# Part11_I2S_WM8960.net
KiCad netlist of a schematic drawn in Altium Designer
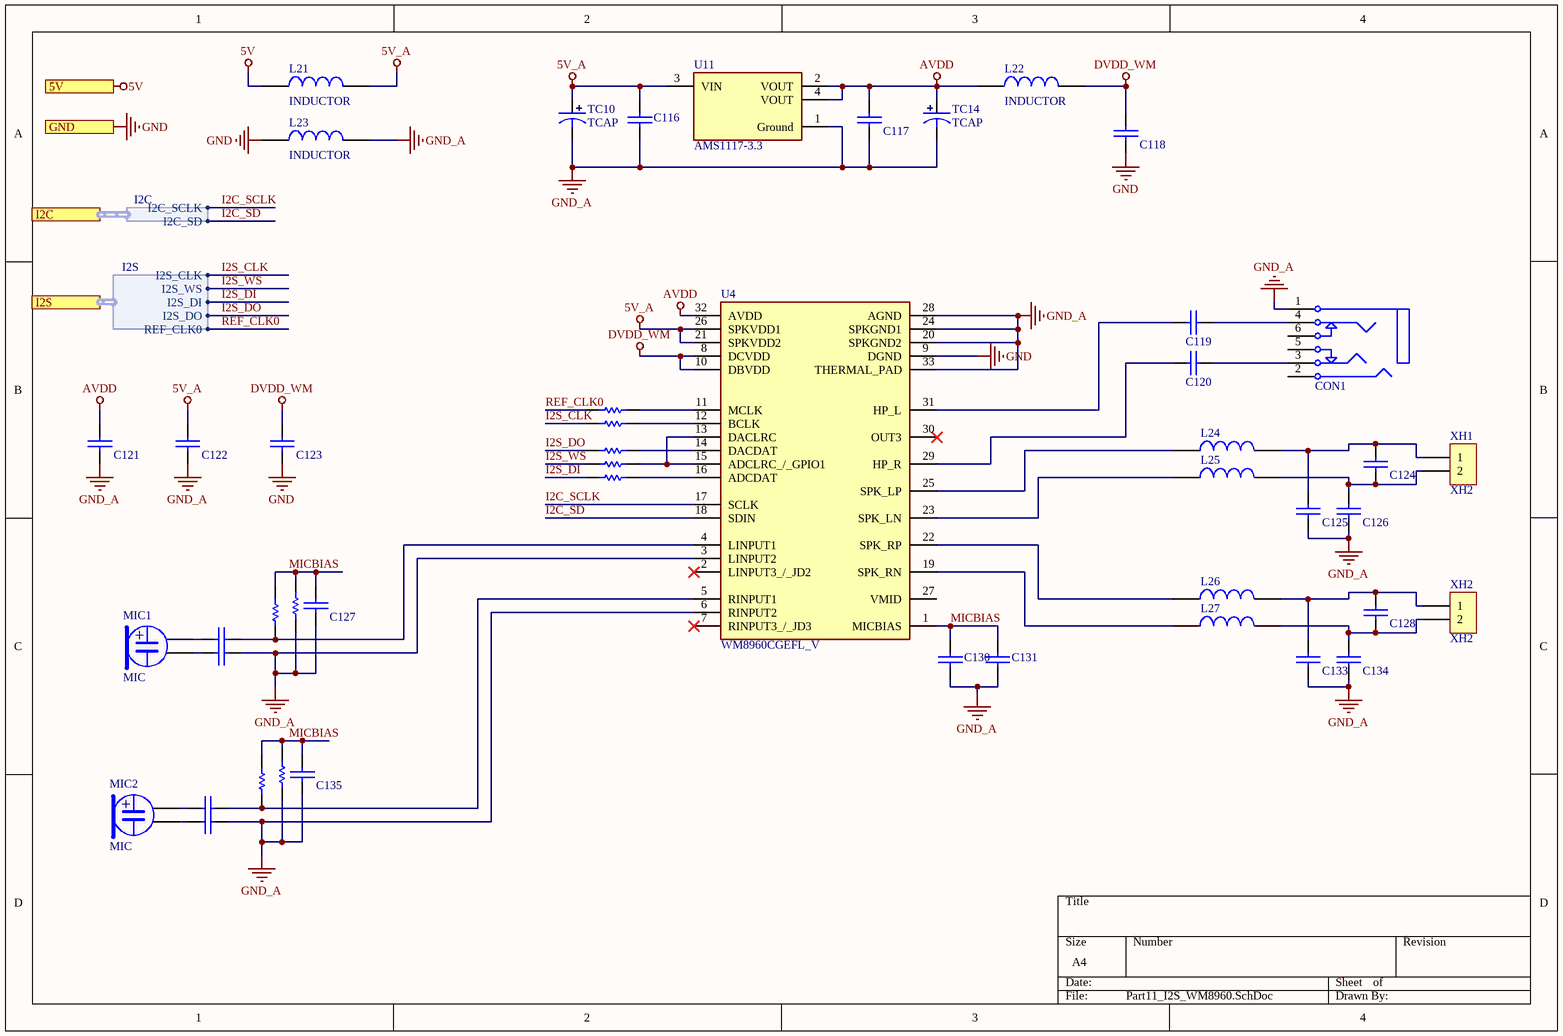
[diagram p0: Part11_I2S_WM8960.SchDoc]

(export (version "E")
  (design (tool "Eeschema 10.0.6"))
  (components
    (comp (ref "C116")
      (value "100nF")
      (footprint "0603C")
      (description "无极性电容")
      (libsource (lib "电容") (part "CAP"))
    )
    (comp (ref "C117")
      (value "100nF")
      (footprint "0603C")
      (description "无极性电容")
      (libsource (lib "电容") (part "CAP"))
    )
    (comp (ref "C118")
      (value "100nF")
      (footprint "0402C")
      (description "无极性电容")
      (libsource (lib "电容") (part "CAP"))
    )
    (comp (ref "C119")
      (value "100nF")
      (footprint "1206C")
      (description "无极性电容")
      (libsource (lib "电容") (part "CAP"))
    )
    (comp (ref "C120")
      (value "100nF")
      (footprint "1206C")
      (description "无极性电容")
      (libsource (lib "电容") (part "CAP"))
    )
    (comp (ref "C121")
      (value "100nF")
      (footprint "0603C")
      (description "无极性电容")
      (libsource (lib "电容") (part "CAP"))
    )
    (comp (ref "C122")
      (value "100nF")
      (footprint "0603C")
      (description "无极性电容")
      (libsource (lib "电容") (part "CAP"))
    )
    (comp (ref "C123")
      (value "100nF")
      (footprint "0603C")
      (description "无极性电容")
      (libsource (lib "电容") (part "CAP"))
    )
    (comp (ref "C124")
      (value "100nF")
      (footprint "1206C")
      (description "无极性电容")
      (libsource (lib "电容") (part "CAP"))
    )
    (comp (ref "C125")
      (value "100nF")
      (footprint "1206C")
      (description "无极性电容")
      (libsource (lib "电容") (part "CAP"))
    )
    (comp (ref "C126")
      (value "100nF")
      (footprint "1206C")
      (description "无极性电容")
      (libsource (lib "电容") (part "CAP"))
    )
    (comp (ref "C127")
      (value "100nF")
      (footprint "0603C")
      (description "无极性电容")
      (libsource (lib "电容") (part "CAP"))
    )
    (comp (ref "C128")
      (value "100nF")
      (footprint "1206C")
      (description "无极性电容")
      (libsource (lib "电容") (part "CAP"))
    )
    (comp (ref "C129")
      (value "100nF")
      (footprint "0603C")
      (description "无极性电容")
      (libsource (lib "电容") (part "CAP"))
    )
    (comp (ref "C130")
      (value "100nF")
      (footprint "0402C")
      (description "无极性电容")
      (libsource (lib "电容") (part "CAP"))
    )
    (comp (ref "C131")
      (value "100nF")
      (footprint "0402C")
      (description "无极性电容")
      (libsource (lib "电容") (part "CAP"))
    )
    (comp (ref "C132")
      (value "100nF")
      (footprint "0603C")
      (description "无极性电容")
      (libsource (lib "电容") (part "CAP"))
    )
    (comp (ref "C133")
      (value "100nF")
      (footprint "1206C")
      (description "无极性电容")
      (libsource (lib "电容") (part "CAP"))
    )
    (comp (ref "C134")
      (value "100nF")
      (footprint "1206C")
      (description "无极性电容")
      (libsource (lib "电容") (part "CAP"))
    )
    (comp (ref "C135")
      (value "100nF")
      (footprint "0603C")
      (description "无极性电容")
      (libsource (lib "电容") (part "CAP"))
    )
    (comp (ref "C136")
      (value "100nF")
      (footprint "0603C")
      (description "无极性电容")
      (libsource (lib "电容") (part "CAP"))
    )
    (comp (ref "C137")
      (value "100nF")
      (footprint "0603C")
      (description "无极性电容")
      (libsource (lib "电容") (part "CAP"))
    )
    (comp (ref "CON1")
      (value "PJ342")
      (footprint "PJ342A")
      (description "3.5耳机插座,4Pin")
      (fields (field (name "版权归属") "源创客"))
      (libsource (lib "音频插座") (part "PJ342"))
    )
    (comp (ref "L21") (value "INDUCTOR") (footprint "0805L") (libsource (lib "电感") (part "INDUCTOR")))
    (comp (ref "L22") (value "INDUCTOR") (footprint "0805L") (libsource (lib "电感") (part "INDUCTOR")))
    (comp (ref "L23") (value "INDUCTOR") (footprint "0805L") (libsource (lib "电感") (part "INDUCTOR")))
    (comp (ref "L24") (value "INDUCTOR") (footprint "0805L") (libsource (lib "电感") (part "INDUCTOR")))
    (comp (ref "L25") (value "INDUCTOR") (footprint "0805L") (libsource (lib "电感") (part "INDUCTOR")))
    (comp (ref "L26") (value "INDUCTOR") (footprint "0805L") (libsource (lib "电感") (part "INDUCTOR")))
    (comp (ref "L27") (value "INDUCTOR") (footprint "0805L") (libsource (lib "电感") (part "INDUCTOR")))
    (comp (ref "MIC1")
      (value "MIC")
      (footprint "MIC-4.5X1.9")
      (description "电容麦克风")
      (libsource (lib "传感器") (part "MIC"))
    )
    (comp (ref "MIC2")
      (value "MIC")
      (footprint "MIC-4.5X1.9")
      (description "电容麦克风")
      (libsource (lib "传感器") (part "MIC"))
    )
    (comp (ref "R21") (value "0R") (footprint "0402R") (libsource (lib "电阻") (part "RES")))
    (comp (ref "R22") (value "0R") (footprint "0402R") (libsource (lib "电阻") (part "RES")))
    (comp (ref "R23") (value "0R") (footprint "0402R") (libsource (lib "电阻") (part "RES")))
    (comp (ref "R24") (value "0R") (footprint "0402R") (libsource (lib "电阻") (part "RES")))
    (comp (ref "R101") (value "0R") (footprint "0402R") (libsource (lib "电阻") (part "RES")))
    (comp (ref "R102") (value "0R") (footprint "0402R") (libsource (lib "电阻") (part "RES")))
    (comp (ref "R103") (value "0R") (footprint "0402R") (libsource (lib "电阻") (part "RES")))
    (comp (ref "R104") (value "0R") (footprint "0402R") (libsource (lib "电阻") (part "RES")))
    (comp (ref "R105") (value "0R") (footprint "0402R") (libsource (lib "电阻") (part "RES")))
    (comp (ref "TC10")
      (value "TCAP")
      (footprint "TAJ-A/3216")
      (description "钽电容")
      (libsource (lib "") (part "TCAP_1"))
    )
    (comp (ref "TC14")
      (value "TCAP")
      (footprint "TAJ-A/3216")
      (description "钽电容")
      (libsource (lib "电容") (part "TCAP"))
    )
    (comp (ref "U4")
      (value "WM8960CGEFL_V")
      (footprint "SamacSys:QFN50P500X500X100-33N")
      (description "Undefined or Miscellaneous")
      (fields (field (name "MANUFACTURER_PART_NUMBER") "WM8960CGEFL/V"))
      (libsource (lib "SamacSys") (part "WM8960CGEFL_V"))
    )
    (comp (ref "U11")
      (value "AMS1117-3.3")
      (footprint "FP-AMS1117-IPC_C")
      (description "LDO Voltage Regulators 1A, 3.3V")
      (fields
        (field (name "OCTOPART") "https://octopart.com/ams1117-3.3-advanced+monolithic+systems-25899300")
        (field (name "MANUFACTURER") "Advanced Monolithic Systems")
      )
      (libsource (lib "Altium Content Vault") (part "8bdbb5f8e77002000e30dd2845d0354"))
    )
    (comp (ref "XH1") (value "XH2") (footprint "XH2/2.54mm/180") (libsource (lib "XH，VH") (part "XH2")))
    (comp (ref "XH2") (value "XH2") (footprint "XH2/2.54mm/180") (libsource (lib "XH，VH") (part "XH2")))
  )
  (nets
    (net (code "3") (name "/I2C_SCLK") (class "Default")
      (node (ref "U4") (pin "17") (pinfunction "SCLK_17") (pintype "passive"))
    )
    (net (code "4") (name "/I2C_SD") (class "Default")
      (node (ref "U4") (pin "18") (pinfunction "SDIN_18") (pintype "passive"))
    )
    (net (code "5") (name "/I2S_CLK") (class "Default")
      (node (ref "R22") (pin "1") (pinfunction "1_1") (pintype "passive"))
    )
    (net (code "6") (name "/I2S_DI") (class "Default")
      (node (ref "R101") (pin "1") (pinfunction "1_1") (pintype "passive"))
    )
    (net (code "7") (name "/I2S_DO") (class "Default")
      (node (ref "R23") (pin "1") (pinfunction "1_1") (pintype "passive"))
    )
    (net (code "8") (name "/I2S_WS") (class "Default")
      (node (ref "R24") (pin "1") (pinfunction "1_1") (pintype "passive"))
    )
    (net (code "9") (name "/MICBIAS") (class "Default")
      (node (ref "C127") (pin "1") (pinfunction "1_1") (pintype "passive"))
      (node (ref "C130") (pin "1") (pinfunction "1_1") (pintype "passive"))
      (node (ref "C131") (pin "1") (pinfunction "1_1") (pintype "passive"))
      (node (ref "C135") (pin "1") (pinfunction "1_1") (pintype "passive"))
      (node (ref "R102") (pin "2") (pinfunction "2_2") (pintype "passive"))
      (node (ref "R103") (pin "2") (pinfunction "2_2") (pintype "passive"))
      (node (ref "R104") (pin "2") (pinfunction "2_2") (pintype "passive"))
      (node (ref "R105") (pin "2") (pinfunction "2_2") (pintype "passive"))
      (node (ref "U4") (pin "1") (pinfunction "MICBIAS_1") (pintype "passive"))
    )
    (net (code "10") (name "/REF_CLK0") (class "Default")
      (node (ref "R21") (pin "1") (pinfunction "1_1") (pintype "passive"))
    )
    (net (code "13") (name "5V") (class "Default")
      (node (ref "L21") (pin "1") (pinfunction "1_1") (pintype "passive"))
    )
    (net (code "14") (name "5V_A") (class "Default")
      (node (ref "C116") (pin "1") (pinfunction "1_1") (pintype "passive"))
      (node (ref "C122") (pin "2") (pinfunction "2_2") (pintype "passive"))
      (node (ref "L21") (pin "2") (pinfunction "2_2") (pintype "passive"))
      (node (ref "TC10") (pin "1") (pinfunction "1_1") (pintype "passive"))
      (node (ref "U11") (pin "3") (pinfunction "VIN_3") (pintype "power_in"))
      (node (ref "U4") (pin "21") (pinfunction "SPKVDD2_21") (pintype "passive"))
      (node (ref "U4") (pin "26") (pinfunction "SPKVDD1_26") (pintype "passive"))
    )
    (net (code "15") (name "AVDD") (class "Default")
      (node (ref "C117") (pin "1") (pinfunction "1_1") (pintype "passive"))
      (node (ref "C121") (pin "2") (pinfunction "2_2") (pintype "passive"))
      (node (ref "L22") (pin "1") (pinfunction "1_1") (pintype "passive"))
      (node (ref "TC14") (pin "1") (pinfunction "1_1") (pintype "passive"))
      (node (ref "U11") (pin "2") (pinfunction "VOUT_2") (pintype "passive"))
      (node (ref "U11") (pin "4") (pinfunction "VOUT_4") (pintype "passive"))
      (node (ref "U4") (pin "32") (pinfunction "AVDD_32") (pintype "passive"))
    )
    (net (code "16") (name "DVDD_WM") (class "Default")
      (node (ref "C118") (pin "1") (pinfunction "1_1") (pintype "passive"))
      (node (ref "C123") (pin "1") (pinfunction "1_1") (pintype "passive"))
      (node (ref "L22") (pin "2") (pinfunction "2_2") (pintype "passive"))
      (node (ref "U4") (pin "10") (pinfunction "DBVDD_10") (pintype "passive"))
      (node (ref "U4") (pin "8") (pinfunction "DCVDD_8") (pintype "passive"))
    )
    (net (code "17") (name "GND") (class "Default")
      (node (ref "C118") (pin "2") (pinfunction "2_2") (pintype "passive"))
      (node (ref "C123") (pin "2") (pinfunction "2_2") (pintype "passive"))
      (node (ref "L23") (pin "1") (pinfunction "1_1") (pintype "passive"))
      (node (ref "U4") (pin "9") (pinfunction "DGND_9") (pintype "passive"))
    )
    (net (code "18") (name "GND_A") (class "Default")
      (node (ref "C116") (pin "2") (pinfunction "2_2") (pintype "passive"))
      (node (ref "C117") (pin "2") (pinfunction "2_2") (pintype "passive"))
      (node (ref "C121") (pin "1") (pinfunction "1_1") (pintype "passive"))
      (node (ref "C122") (pin "1") (pinfunction "1_1") (pintype "passive"))
      (node (ref "C125") (pin "1") (pinfunction "1_1") (pintype "passive"))
      (node (ref "C126") (pin "1") (pinfunction "1_1") (pintype "passive"))
      (node (ref "C127") (pin "2") (pinfunction "2_2") (pintype "passive"))
      (node (ref "C130") (pin "2") (pinfunction "2_2") (pintype "passive"))
      (node (ref "C131") (pin "2") (pinfunction "2_2") (pintype "passive"))
      (node (ref "C132") (pin "1") (pinfunction "1_1") (pintype "passive"))
      (node (ref "C133") (pin "1") (pinfunction "1_1") (pintype "passive"))
      (node (ref "C134") (pin "1") (pinfunction "1_1") (pintype "passive"))
      (node (ref "C135") (pin "2") (pinfunction "2_2") (pintype "passive"))
      (node (ref "C137") (pin "1") (pinfunction "1_1") (pintype "passive"))
      (node (ref "CON1") (pin "1") (pinfunction "1_1") (pintype "passive"))
      (node (ref "L23") (pin "2") (pinfunction "2_2") (pintype "passive"))
      (node (ref "R102") (pin "1") (pinfunction "1_1") (pintype "passive"))
      (node (ref "R104") (pin "1") (pinfunction "1_1") (pintype "passive"))
      (node (ref "TC10") (pin "2") (pinfunction "2_2") (pintype "passive"))
      (node (ref "TC14") (pin "2") (pinfunction "2_2") (pintype "passive"))
      (node (ref "U11") (pin "1") (pinfunction "Ground_1") (pintype "power_in"))
      (node (ref "U4") (pin "20") (pinfunction "SPKGND2_20") (pintype "passive"))
      (node (ref "U4") (pin "24") (pinfunction "SPKGND1_24") (pintype "passive"))
      (node (ref "U4") (pin "28") (pinfunction "AGND_28") (pintype "passive"))
      (node (ref "U4") (pin "3") (pinfunction "LINPUT2_3") (pintype "passive"))
      (node (ref "U4") (pin "33") (pinfunction "THERMAL_PAD_33") (pintype "passive"))
      (node (ref "U4") (pin "6") (pinfunction "RINPUT2_6") (pintype "passive"))
    )
    (net (code "19") (name "Net-(C119-Pad1)") (class "Default")
      (node (ref "C119") (pin "1") (pinfunction "1_1") (pintype "passive"))
      (node (ref "CON1") (pin "4") (pinfunction "4_4") (pintype "passive"))
    )
    (net (code "20") (name "Net-(C120-Pad1)") (class "Default")
      (node (ref "C120") (pin "1") (pinfunction "1_1") (pintype "passive"))
      (node (ref "CON1") (pin "3") (pinfunction "3_3") (pintype "passive"))
    )
    (net (code "21") (name "Net-(C124-Pad1)") (class "Default")
      (node (ref "C124") (pin "1") (pinfunction "1_1") (pintype "passive"))
      (node (ref "C126") (pin "2") (pinfunction "2_2") (pintype "passive"))
      (node (ref "L25") (pin "2") (pinfunction "2_2") (pintype "passive"))
      (node (ref "XH1") (pin "2") (pinfunction "2_2") (pintype "passive"))
    )
    (net (code "22") (name "Net-(C124-Pad2)") (class "Default")
      (node (ref "C124") (pin "2") (pinfunction "2_2") (pintype "passive"))
      (node (ref "C125") (pin "2") (pinfunction "2_2") (pintype "passive"))
      (node (ref "L24") (pin "2") (pinfunction "2_2") (pintype "passive"))
      (node (ref "XH1") (pin "1") (pinfunction "1_1") (pintype "passive"))
    )
    (net (code "23") (name "Net-(C128-Pad1)") (class "Default")
      (node (ref "C128") (pin "1") (pinfunction "1_1") (pintype "passive"))
      (node (ref "C134") (pin "2") (pinfunction "2_2") (pintype "passive"))
      (node (ref "L27") (pin "2") (pinfunction "2_2") (pintype "passive"))
      (node (ref "XH2") (pin "2") (pinfunction "2_2") (pintype "passive"))
    )
    (net (code "24") (name "Net-(C128-Pad2)") (class "Default")
      (node (ref "C128") (pin "2") (pinfunction "2_2") (pintype "passive"))
      (node (ref "C133") (pin "2") (pinfunction "2_2") (pintype "passive"))
      (node (ref "L26") (pin "2") (pinfunction "2_2") (pintype "passive"))
      (node (ref "XH2") (pin "1") (pinfunction "1_1") (pintype "passive"))
    )
    (net (code "25") (name "Net-(C129-Pad2)") (class "Default")
      (node (ref "C129") (pin "2") (pinfunction "2_2") (pintype "passive"))
      (node (ref "MIC1") (pin "1") (pinfunction "1_1") (pintype "passive"))
    )
    (net (code "26") (name "Net-(C132-Pad2)") (class "Default")
      (node (ref "C132") (pin "2") (pinfunction "2_2") (pintype "passive"))
      (node (ref "MIC1") (pin "2") (pinfunction "2_2") (pintype "passive"))
    )
    (net (code "27") (name "Net-(C136-Pad2)") (class "Default")
      (node (ref "C136") (pin "2") (pinfunction "2_2") (pintype "passive"))
      (node (ref "MIC2") (pin "1") (pinfunction "1_1") (pintype "passive"))
    )
    (net (code "28") (name "Net-(C137-Pad2)") (class "Default")
      (node (ref "C137") (pin "2") (pinfunction "2_2") (pintype "passive"))
      (node (ref "MIC2") (pin "2") (pinfunction "2_2") (pintype "passive"))
    )
    (net (code "29") (name "Net-(U4-ADCDAT)") (class "Default")
      (node (ref "R101") (pin "2") (pinfunction "2_2") (pintype "passive"))
      (node (ref "U4") (pin "16") (pinfunction "ADCDAT_16") (pintype "passive"))
    )
    (net (code "30") (name "Net-(U4-ADCLRC_{slash}_GPIO1)") (class "Default")
      (node (ref "R24") (pin "2") (pinfunction "2_2") (pintype "passive"))
      (node (ref "U4") (pin "13") (pinfunction "DACLRC_13") (pintype "passive"))
      (node (ref "U4") (pin "15") (pinfunction "ADCLRC_/_GPIO1_15") (pintype "passive"))
    )
    (net (code "31") (name "Net-(U4-BCLK)") (class "Default")
      (node (ref "R22") (pin "2") (pinfunction "2_2") (pintype "passive"))
      (node (ref "U4") (pin "12") (pinfunction "BCLK_12") (pintype "passive"))
    )
    (net (code "32") (name "Net-(U4-DACDAT)") (class "Default")
      (node (ref "R23") (pin "2") (pinfunction "2_2") (pintype "passive"))
      (node (ref "U4") (pin "14") (pinfunction "DACDAT_14") (pintype "passive"))
    )
    (net (code "33") (name "Net-(U4-HP_L)") (class "Default")
      (node (ref "C119") (pin "2") (pinfunction "2_2") (pintype "passive"))
      (node (ref "U4") (pin "31") (pinfunction "HP_L_31") (pintype "passive"))
    )
    (net (code "34") (name "Net-(U4-HP_R)") (class "Default")
      (node (ref "C120") (pin "2") (pinfunction "2_2") (pintype "passive"))
      (node (ref "U4") (pin "29") (pinfunction "HP_R_29") (pintype "passive"))
    )
    (net (code "35") (name "Net-(U4-LINPUT1)") (class "Default")
      (node (ref "C129") (pin "1") (pinfunction "1_1") (pintype "passive"))
      (node (ref "R103") (pin "1") (pinfunction "1_1") (pintype "passive"))
      (node (ref "U4") (pin "4") (pinfunction "LINPUT1_4") (pintype "passive"))
    )
    (net (code "36") (name "Net-(U4-MCLK)") (class "Default")
      (node (ref "R21") (pin "2") (pinfunction "2_2") (pintype "passive"))
      (node (ref "U4") (pin "11") (pinfunction "MCLK_11") (pintype "passive"))
    )
    (net (code "37") (name "Net-(U4-RINPUT1)") (class "Default")
      (node (ref "C136") (pin "1") (pinfunction "1_1") (pintype "passive"))
      (node (ref "R105") (pin "1") (pinfunction "1_1") (pintype "passive"))
      (node (ref "U4") (pin "5") (pinfunction "RINPUT1_5") (pintype "passive"))
    )
    (net (code "38") (name "Net-(U4-SPK_LN)") (class "Default")
      (node (ref "L25") (pin "1") (pinfunction "1_1") (pintype "passive"))
      (node (ref "U4") (pin "23") (pinfunction "SPK_LN_23") (pintype "passive"))
    )
    (net (code "39") (name "Net-(U4-SPK_LP)") (class "Default")
      (node (ref "L24") (pin "1") (pinfunction "1_1") (pintype "passive"))
      (node (ref "U4") (pin "25") (pinfunction "SPK_LP_25") (pintype "passive"))
    )
    (net (code "40") (name "Net-(U4-SPK_RN)") (class "Default")
      (node (ref "L27") (pin "1") (pinfunction "1_1") (pintype "passive"))
      (node (ref "U4") (pin "19") (pinfunction "SPK_RN_19") (pintype "passive"))
    )
    (net (code "41") (name "Net-(U4-SPK_RP)") (class "Default")
      (node (ref "L26") (pin "1") (pinfunction "1_1") (pintype "passive"))
      (node (ref "U4") (pin "22") (pinfunction "SPK_RP_22") (pintype "passive"))
    )
    (net (code "42") (name "unconnected-(CON1-Pad2)") (class "Default")
      (node (ref "CON1") (pin "2") (pinfunction "2_2") (pintype "passive"))
    )
    (net (code "43") (name "unconnected-(CON1-Pad5)") (class "Default")
      (node (ref "CON1") (pin "5") (pinfunction "5_5") (pintype "passive"))
    )
    (net (code "44") (name "unconnected-(CON1-Pad6)") (class "Default")
      (node (ref "CON1") (pin "6") (pinfunction "6_6") (pintype "passive"))
    )
    (net (code "45") (name "unconnected-(U4-LINPUT3_{slash}_JD2-Pad2)") (class "Default")
      (node (ref "U4") (pin "2") (pinfunction "LINPUT3_/_JD2_2") (pintype "passive+no_connect"))
    )
    (net (code "46") (name "unconnected-(U4-OUT3-Pad30)") (class "Default")
      (node (ref "U4") (pin "30") (pinfunction "OUT3_30") (pintype "passive+no_connect"))
    )
    (net (code "47") (name "unconnected-(U4-RINPUT3_{slash}_JD3-Pad7)") (class "Default")
      (node (ref "U4") (pin "7") (pinfunction "RINPUT3_/_JD3_7") (pintype "passive+no_connect"))
    )
    (net (code "48") (name "unconnected-(U4-VMID-Pad27)") (class "Default")
      (node (ref "U4") (pin "27") (pinfunction "VMID_27") (pintype "passive"))
    )
  )
)
